# OBC_v4_22.net
KiCad netlist of a schematic drawn in EAGLE
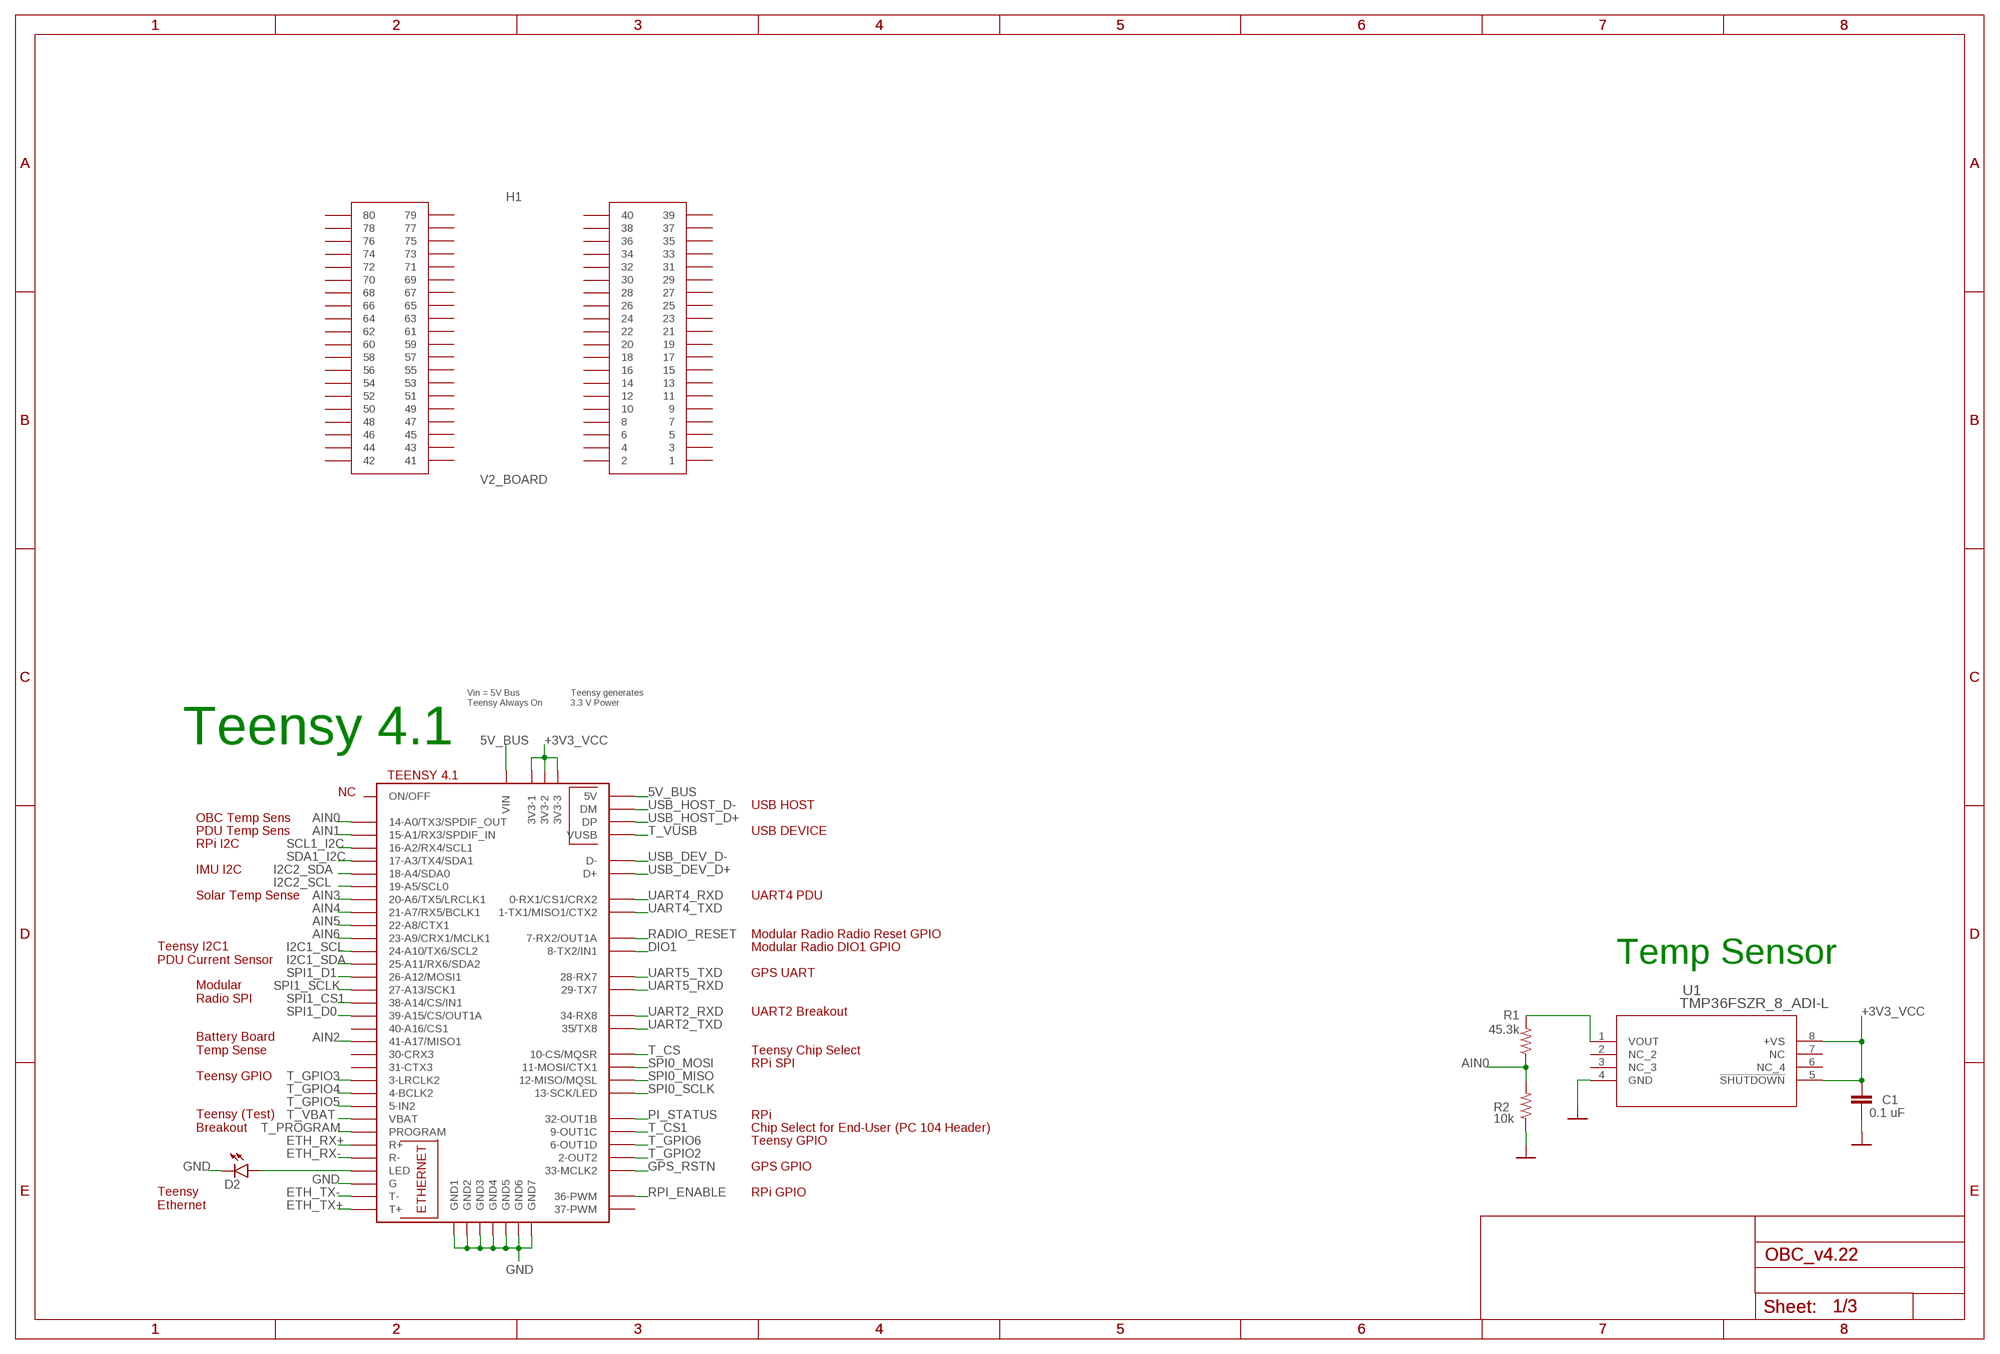
[diagram p0: schematic, sheet 1]
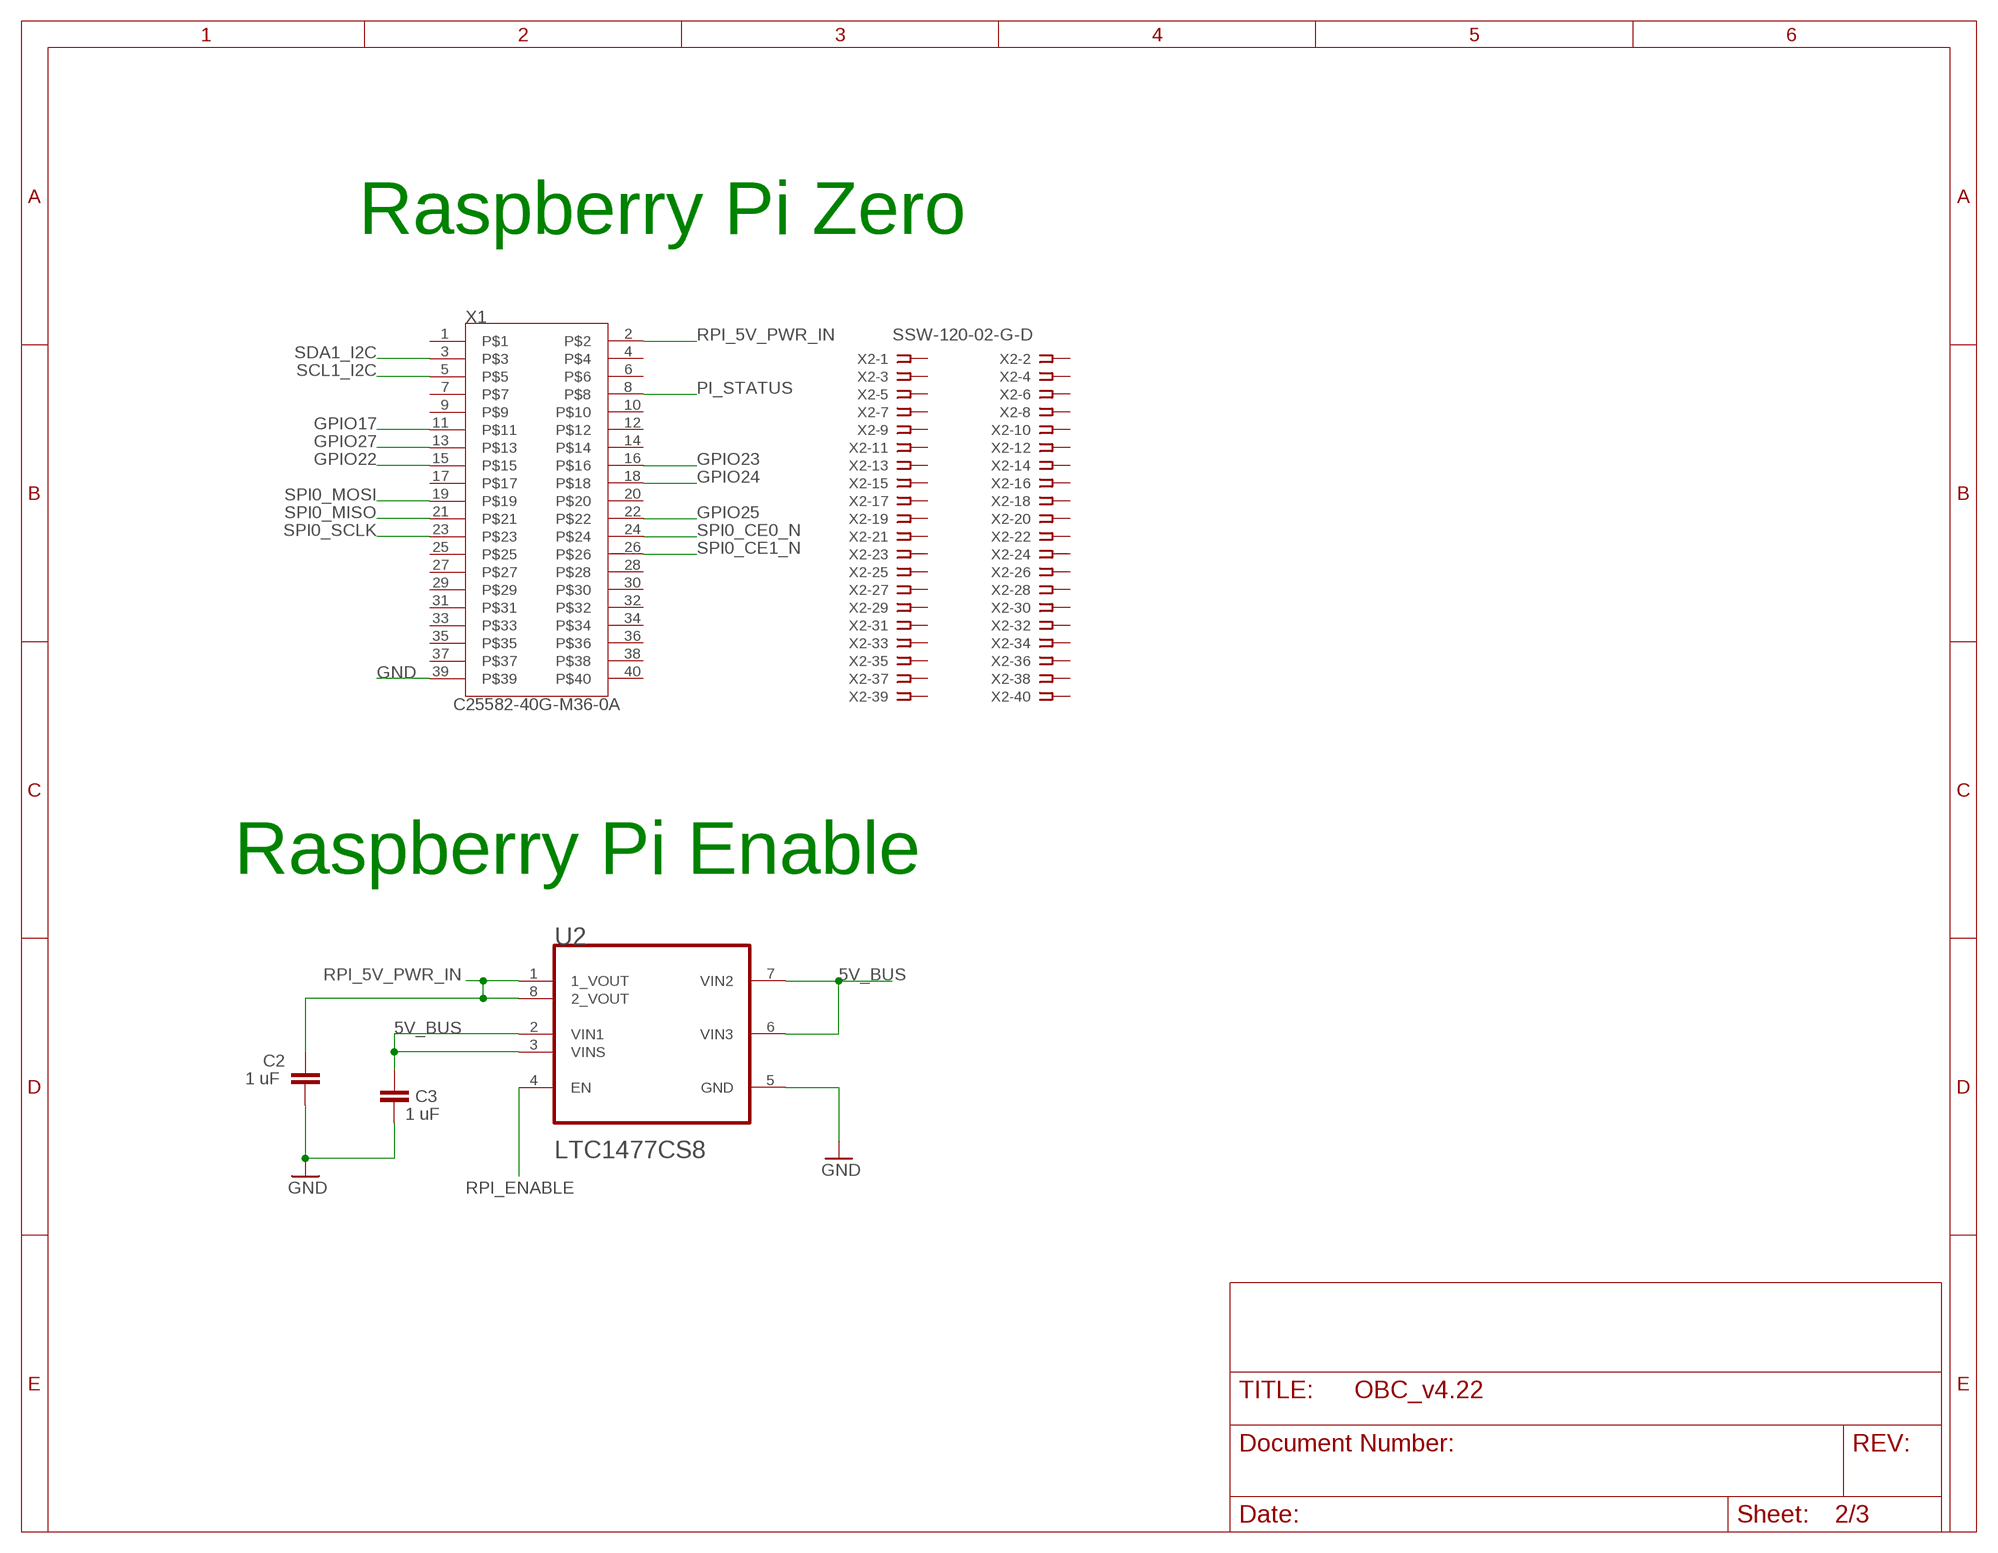
[diagram p1: schematic, sheet 2]
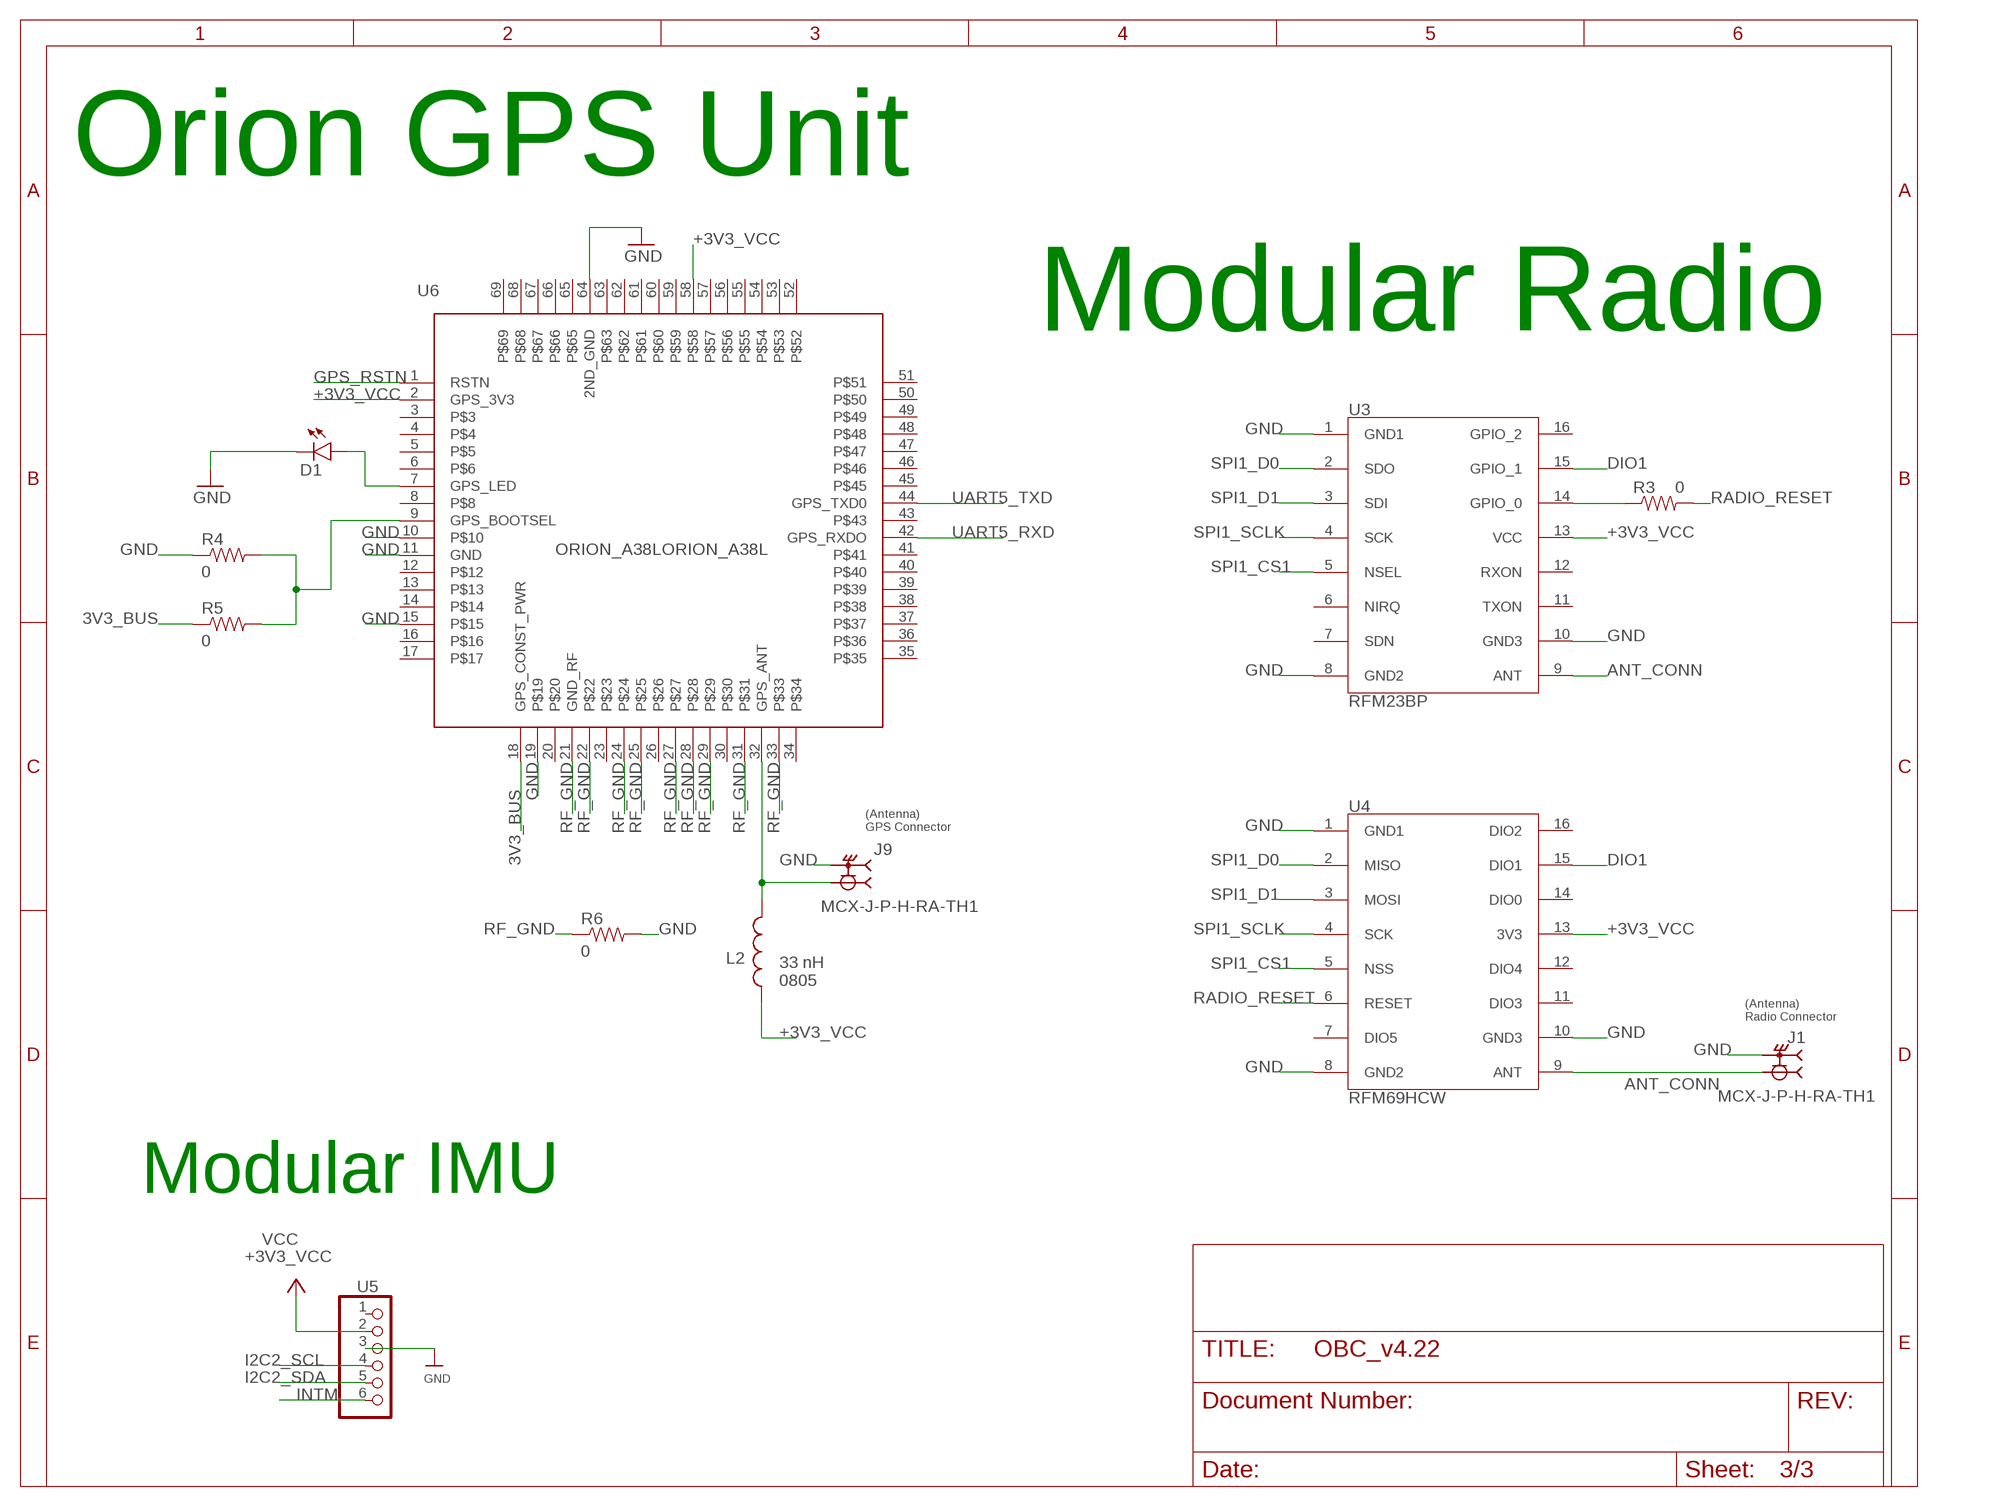
[diagram p2: schematic, sheet 3]

(export (version "E")
  (design (tool "Eeschema 10.0.6"))
  (components
    (comp (ref "C2")
      (value "1 uF")
      (footprint "eagle-import:0805")
      (libsource (lib "eagle-import") (part "CAP0805"))
    )
    (comp (ref "C3")
      (value "1 uF")
      (footprint "eagle-import:0805")
      (libsource (lib "eagle-import") (part "CAP0805"))
    )
    (comp (ref "U2")
      (value "LTC1477CS8LINEAR_TECHNOLOGY_LTC1477CS8_0_2")
      (footprint "eagle-import:LINEAR_TECHNOLOGY_LTC1477CS8_2")
      (fields (field (name "MF") "Linear Technology") (field (name "MPN") "LTC1477CS8"))
      (libsource (lib "eagle-import") (part "LTC1477CS8LINEAR_TECHNOLOGY_LTC1477CS8_0_2"))
    )
    (comp (ref "X1")
      (value "C25582-40G-M36-0A")
      (footprint "eagle-import:ADAFRUIT_C25582-40G-M36-0A_0")
      (libsource (lib "eagle-import") (part "C25582-40G-M36-0A"))
    )
    (comp (ref "X2")
      (value "SSW-120-02-G-D")
      (footprint "eagle-import:SSW-120-02-G-D")
      (fields (field (name "MF") "Samtec Inc."))
      (libsource (lib "eagle-import") (part "SSW-120-02-G-D"))
    )
    (comp (ref "C1")
      (value "0.1 uF")
      (footprint "eagle-import:0805")
      (libsource (lib "eagle-import") (part "CAP0805"))
    )
    (comp (ref "D2")
      (value "LEDCHIP-LED0603")
      (footprint "eagle-import:CHIP-LED0603")
      (libsource (lib "eagle-import") (part "LEDCHIP-LED0603"))
    )
    (comp (ref "H1")
      (value "V2_BOARD")
      (footprint "eagle-import:BOARD_TEMPLATE")
      (libsource (lib "eagle-import") (part "V2_BOARD"))
    )
    (comp (ref "R1")
      (value "45.3k")
      (footprint "eagle-import:0805")
      (libsource (lib "eagle-import") (part "RESISTOR0805-RES"))
    )
    (comp (ref "R2")
      (value "10k")
      (footprint "eagle-import:0805")
      (libsource (lib "eagle-import") (part "RESISTOR0805-RES"))
    )
    (comp (ref "U$1")
      (value "TEENSY41TEENSY")
      (footprint "eagle-import:TEENSY41")
      (libsource (lib "eagle-import") (part "TEENSY41TEENSY"))
    )
    (comp (ref "U1")
      (value "TMP36FSZR_8_ADI-L")
      (footprint "eagle-import:R_8_ADI-L")
      (fields
        (field (name "MANUFACTURER_PART_NUMBER") "TMP36FSZ")
        (field (name "COPYRIGHT") "Copyright (C) 2021 Ultra Librarian. All rights reserved.")
      )
      (libsource (lib "eagle-import") (part "TMP36FSZR_8_ADI-L"))
    )
    (comp (ref "D1")
      (value "LEDCHIP-LED0603")
      (footprint "eagle-import:CHIP-LED0603")
      (libsource (lib "eagle-import") (part "LEDCHIP-LED0603"))
    )
    (comp (ref "J1")
      (value "MCX-J-P-H-RA-TH1")
      (footprint "eagle-import:SAMTEC_MCX-J-P-H-RA-TH1")
      (fields (field (name "DIGI-KEY_PART_NUMBER") "SAM10607-ND") (field (name "MF") "Samtec"))
      (libsource (lib "eagle-import") (part "MCX-J-P-H-RA-TH1"))
    )
    (comp (ref "J9")
      (value "MCX-J-P-H-RA-TH1")
      (footprint "eagle-import:SAMTEC_MCX-J-P-H-RA-TH1")
      (fields (field (name "DIGI-KEY_PART_NUMBER") "SAM10607-ND") (field (name "MF") "Samtec"))
      (libsource (lib "eagle-import") (part "MCX-J-P-H-RA-TH1"))
    )
    (comp (ref "L2")
      (value "AIMC-0805-2N2S-T")
      (footprint "eagle-import:INDC2012X105N")
      (fields (field (name "DIGI-KEY_PART_NUMBER") "535-11562-1-ND") (field (name "MF") "Abracon"))
      (libsource (lib "eagle-import") (part "AIMC-0805-2N2S-T"))
    )
    (comp (ref "R3")
      (value "0")
      (footprint "eagle-import:0805")
      (libsource (lib "eagle-import") (part "RESISTOR0805-RES"))
    )
    (comp (ref "R4")
      (value "0")
      (footprint "eagle-import:0805")
      (libsource (lib "eagle-import") (part "RESISTOR0805-RES"))
    )
    (comp (ref "R5")
      (value "0")
      (footprint "eagle-import:0805")
      (libsource (lib "eagle-import") (part "RESISTOR0805-RES"))
    )
    (comp (ref "R6")
      (value "0")
      (footprint "eagle-import:0805")
      (libsource (lib "eagle-import") (part "RESISTOR0805-RES"))
    )
    (comp (ref "U3")
      (value "RFM23BP")
      (footprint "eagle-import:RFM23BP")
      (libsource (lib "eagle-import") (part "RFM23BP"))
    )
    (comp (ref "U4")
      (value "RFM69HCW")
      (footprint "eagle-import:RFM69HCW")
      (libsource (lib "eagle-import") (part "RFM69HCW"))
    )
    (comp (ref "U5")
      (value "HEADER-1X670MIL")
      (footprint "eagle-import:1X06_ROUND_70")
      (libsource (lib "eagle-import") (part "HEADER-1X670MIL"))
    )
    (comp (ref "U6")
      (value "ORION_A38LORION_A38L")
      (footprint "eagle-import:ORION_A38L")
      (libsource (lib "eagle-import") (part "ORION_A38LORION_A38L"))
    )
  )
  (nets
    (net (code "1") (name "+3V3_VCC") (class "Default")
      (node (ref "C1") (pin "1") (pinfunction "1_1") (pintype "passive"))
      (node (ref "L2") (pin "1") (pinfunction "1_1") (pintype "passive"))
      (node (ref "U$1") (pin "3V3-1") (pinfunction "3V3-1_3V3-1") (pintype "bidirectional"))
      (node (ref "U$1") (pin "3V3-2") (pinfunction "3V3-2_3V3-2") (pintype "bidirectional"))
      (node (ref "U$1") (pin "3V3-3") (pinfunction "3V3-3_3V3-3") (pintype "bidirectional"))
      (node (ref "U1") (pin "5") (pinfunction "~{SHUTDOWN}_5") (pintype "passive"))
      (node (ref "U1") (pin "8") (pinfunction "+VS_8") (pintype "power_in"))
      (node (ref "U3") (pin "13") (pinfunction "VCC_13") (pintype "bidirectional"))
      (node (ref "U4") (pin "13") (pinfunction "3V3_13") (pintype "bidirectional"))
      (node (ref "U5") (pin "2") (pinfunction "2_2") (pintype "passive"))
      (node (ref "U6") (pin "2") (pinfunction "GPS_3V3_2") (pintype "bidirectional"))
      (node (ref "U6") (pin "58") (pinfunction "P$58_58") (pintype "bidirectional"))
    )
    (net (code "2") (name "3V3_BUS") (class "Default")
      (node (ref "R5") (pin "1") (pinfunction "1_1") (pintype "passive"))
      (node (ref "U6") (pin "18") (pinfunction "GPS_CONST_PWR_18") (pintype "bidirectional"))
    )
    (net (code "3") (name "5V_BUS") (class "Default")
      (node (ref "C3") (pin "1") (pinfunction "1_1") (pintype "passive"))
      (node (ref "U$1") (pin "+5V") (pinfunction "5V_+5V") (pintype "bidirectional"))
      (node (ref "U$1") (pin "VIN") (pinfunction "VIN_VIN") (pintype "bidirectional"))
      (node (ref "U2") (pin "2") (pinfunction "VIN1_2") (pintype "power_in"))
      (node (ref "U2") (pin "3") (pinfunction "VINS_3") (pintype "power_in"))
      (node (ref "U2") (pin "6") (pinfunction "VIN3_6") (pintype "power_in"))
      (node (ref "U2") (pin "7") (pinfunction "VIN2_7") (pintype "power_in"))
    )
    (net (code "4") (name "AIN0") (class "Default")
      (node (ref "R1") (pin "1") (pinfunction "1_1") (pintype "passive"))
      (node (ref "R2") (pin "2") (pinfunction "2_2") (pintype "passive"))
      (node (ref "U$1") (pin "14-A0/TX3/SPDIF_OUT") (pinfunction "14-A0/TX3/SPDIF_OUT_14-A0/TX3/SPDIF_OUT") (pintype "bidirectional"))
    )
    (net (code "5") (name "AIN1") (class "Default")
      (node (ref "U$1") (pin "15-A1/RX3/SPDIF_IN") (pinfunction "15-A1/RX3/SPDIF_IN_15-A1/RX3/SPDIF_IN") (pintype "bidirectional"))
    )
    (net (code "6") (name "AIN2") (class "Default")
      (node (ref "U$1") (pin "41-A17/MISO1") (pinfunction "41-A17/MISO1_41-A17/MISO1") (pintype "bidirectional"))
    )
    (net (code "7") (name "AIN3") (class "Default")
      (node (ref "U$1") (pin "20-A6/TX5/LRCLK1") (pinfunction "20-A6/TX5/LRCLK1_20-A6/TX5/LRCLK1") (pintype "bidirectional"))
    )
    (net (code "8") (name "AIN4") (class "Default")
      (node (ref "U$1") (pin "21-A7/RX5/BCLK1") (pinfunction "21-A7/RX5/BCLK1_21-A7/RX5/BCLK1") (pintype "bidirectional"))
    )
    (net (code "9") (name "AIN5") (class "Default")
      (node (ref "U$1") (pin "22-A8/CTX1") (pinfunction "22-A8/CTX1_22-A8/CTX1") (pintype "bidirectional"))
    )
    (net (code "10") (name "AIN6") (class "Default")
      (node (ref "U$1") (pin "23-A9/CRX1/MCLK1") (pinfunction "23-A9/CRX1/MCLK1_23-A9/CRX1/MCLK1") (pintype "bidirectional"))
    )
    (net (code "11") (name "ANT_CONN") (class "Default")
      (node (ref "J1") (pin "1") (pinfunction "1_1") (pintype "passive"))
      (node (ref "U3") (pin "9") (pinfunction "ANT_9") (pintype "bidirectional"))
      (node (ref "U4") (pin "9") (pinfunction "ANT_9") (pintype "bidirectional"))
    )
    (net (code "12") (name "DIO1") (class "Default")
      (node (ref "U$1") (pin "8-TX2/IN1") (pinfunction "8-TX2/IN1_8-TX2/IN1") (pintype "bidirectional"))
      (node (ref "U3") (pin "15") (pinfunction "GPIO_1_15") (pintype "bidirectional"))
      (node (ref "U4") (pin "15") (pinfunction "DIO1_15") (pintype "bidirectional"))
    )
    (net (code "13") (name "ETH_RX+") (class "Default")
      (node (ref "U$1") (pin "R+") (pinfunction "R+_R+") (pintype "bidirectional"))
    )
    (net (code "14") (name "ETH_RX-") (class "Default")
      (node (ref "U$1") (pin "R-") (pinfunction "R-_R-") (pintype "bidirectional"))
    )
    (net (code "15") (name "ETH_TX+") (class "Default")
      (node (ref "U$1") (pin "T+") (pinfunction "T+_T+") (pintype "bidirectional"))
    )
    (net (code "16") (name "ETH_TX-") (class "Default")
      (node (ref "U$1") (pin "T-") (pinfunction "T-_T-") (pintype "bidirectional"))
    )
    (net (code "17") (name "GND") (class "Default")
      (node (ref "C1") (pin "2") (pinfunction "2_2") (pintype "passive"))
      (node (ref "C2") (pin "2") (pinfunction "2_2") (pintype "passive"))
      (node (ref "C3") (pin "2") (pinfunction "2_2") (pintype "passive"))
      (node (ref "D1") (pin "C") (pinfunction "C_C") (pintype "passive"))
      (node (ref "D2") (pin "C") (pinfunction "C_C") (pintype "passive"))
      (node (ref "J1") (pin "S1") (pinfunction "2_S1") (pintype "passive"))
      (node (ref "J1") (pin "S2") (pinfunction "2_S2") (pintype "passive"))
      (node (ref "J1") (pin "S3") (pinfunction "2_S3") (pintype "passive"))
      (node (ref "J1") (pin "S4") (pinfunction "2_S4") (pintype "passive"))
      (node (ref "J9") (pin "S1") (pinfunction "2_S1") (pintype "passive"))
      (node (ref "J9") (pin "S2") (pinfunction "2_S2") (pintype "passive"))
      (node (ref "J9") (pin "S3") (pinfunction "2_S3") (pintype "passive"))
      (node (ref "J9") (pin "S4") (pinfunction "2_S4") (pintype "passive"))
      (node (ref "R2") (pin "1") (pinfunction "1_1") (pintype "passive"))
      (node (ref "R4") (pin "1") (pinfunction "1_1") (pintype "passive"))
      (node (ref "R6") (pin "2") (pinfunction "2_2") (pintype "passive"))
      (node (ref "U$1") (pin "G") (pinfunction "G_G") (pintype "bidirectional"))
      (node (ref "U$1") (pin "GND") (pinfunction "GND7_GND") (pintype "bidirectional"))
      (node (ref "U$1") (pin "GND1") (pinfunction "GND1_GND1") (pintype "bidirectional"))
      (node (ref "U$1") (pin "GND2") (pinfunction "GND2_GND2") (pintype "bidirectional"))
      (node (ref "U$1") (pin "GND3") (pinfunction "GND3_GND3") (pintype "bidirectional"))
      (node (ref "U$1") (pin "GND4") (pinfunction "GND4_GND4") (pintype "bidirectional"))
      (node (ref "U$1") (pin "GND5") (pinfunction "GND5_GND5") (pintype "bidirectional"))
      (node (ref "U$1") (pin "GND6") (pinfunction "GND6_GND6") (pintype "bidirectional"))
      (node (ref "U1") (pin "4") (pinfunction "GND_4") (pintype "passive"))
      (node (ref "U2") (pin "5") (pinfunction "GND_5") (pintype "power_in"))
      (node (ref "U3") (pin "1") (pinfunction "GND1_1") (pintype "bidirectional"))
      (node (ref "U3") (pin "10") (pinfunction "GND3_10") (pintype "bidirectional"))
      (node (ref "U3") (pin "8") (pinfunction "GND2_8") (pintype "bidirectional"))
      (node (ref "U4") (pin "1") (pinfunction "GND1_1") (pintype "bidirectional"))
      (node (ref "U4") (pin "10") (pinfunction "GND3_10") (pintype "bidirectional"))
      (node (ref "U4") (pin "8") (pinfunction "GND2_8") (pintype "bidirectional"))
      (node (ref "U5") (pin "3") (pinfunction "3_3") (pintype "passive"))
      (node (ref "U6") (pin "10") (pinfunction "P$10_10") (pintype "bidirectional"))
      (node (ref "U6") (pin "11") (pinfunction "GND_11") (pintype "bidirectional"))
      (node (ref "U6") (pin "15") (pinfunction "P$15_15") (pintype "bidirectional"))
      (node (ref "U6") (pin "19") (pinfunction "P$19_19") (pintype "bidirectional"))
      (node (ref "U6") (pin "64") (pinfunction "2ND_GND_64") (pintype "bidirectional"))
      (node (ref "X1") (pin "39") (pinfunction "P$39_39") (pintype "bidirectional"))
    )
    (net (code "18") (name "GPIO17") (class "Default")
      (node (ref "X1") (pin "11") (pinfunction "P$11_11") (pintype "bidirectional"))
    )
    (net (code "19") (name "GPIO22") (class "Default")
      (node (ref "X1") (pin "15") (pinfunction "P$15_15") (pintype "bidirectional"))
    )
    (net (code "20") (name "GPIO23") (class "Default")
      (node (ref "X1") (pin "16") (pinfunction "P$16_16") (pintype "bidirectional"))
    )
    (net (code "21") (name "GPIO24") (class "Default")
      (node (ref "X1") (pin "18") (pinfunction "P$18_18") (pintype "bidirectional"))
    )
    (net (code "22") (name "GPIO25") (class "Default")
      (node (ref "X1") (pin "22") (pinfunction "P$22_22") (pintype "bidirectional"))
    )
    (net (code "23") (name "GPIO27") (class "Default")
      (node (ref "X1") (pin "13") (pinfunction "P$13_13") (pintype "bidirectional"))
    )
    (net (code "24") (name "GPS_RSTN") (class "Default")
      (node (ref "U$1") (pin "33-MCLK2") (pinfunction "33-MCLK2_33-MCLK2") (pintype "bidirectional"))
      (node (ref "U6") (pin "1") (pinfunction "RSTN_1") (pintype "bidirectional"))
    )
    (net (code "25") (name "I2C1_SCL") (class "Default")
      (node (ref "U$1") (pin "24-A10/TX6/SCL2") (pinfunction "24-A10/TX6/SCL2_24-A10/TX6/SCL2") (pintype "bidirectional"))
    )
    (net (code "26") (name "I2C1_SDA") (class "Default")
      (node (ref "U$1") (pin "25-A11/RX6/SDA2") (pinfunction "25-A11/RX6/SDA2_25-A11/RX6/SDA2") (pintype "bidirectional"))
    )
    (net (code "27") (name "I2C2_SCL") (class "Default")
      (node (ref "U$1") (pin "19-A5/SCL0") (pinfunction "19-A5/SCL0_19-A5/SCL0") (pintype "bidirectional"))
      (node (ref "U5") (pin "4") (pinfunction "4_4") (pintype "passive"))
    )
    (net (code "28") (name "I2C2_SDA") (class "Default")
      (node (ref "U$1") (pin "18-A4/SDA0") (pinfunction "18-A4/SDA0_18-A4/SDA0") (pintype "bidirectional"))
      (node (ref "U5") (pin "5") (pinfunction "5_5") (pintype "passive"))
    )
    (net (code "29") (name "INTM") (class "Default")
      (node (ref "U5") (pin "6") (pinfunction "6_6") (pintype "passive"))
    )
    (net (code "30") (name "Net-(D2-PadA)") (class "Default")
      (node (ref "D2") (pin "A") (pinfunction "A_A") (pintype "passive"))
      (node (ref "U$1") (pin "LED") (pinfunction "LED_LED") (pintype "bidirectional"))
    )
    (net (code "31") (name "Net-(U1-VOUT)") (class "Default")
      (node (ref "R1") (pin "2") (pinfunction "2_2") (pintype "passive"))
      (node (ref "U1") (pin "1") (pinfunction "VOUT_1") (pintype "output"))
    )
    (net (code "32") (name "Net-(U3-GPIO_0)") (class "Default")
      (node (ref "R3") (pin "1") (pinfunction "1_1") (pintype "passive"))
      (node (ref "U3") (pin "14") (pinfunction "GPIO_0_14") (pintype "bidirectional"))
    )
    (net (code "33") (name "Net-(U6-GPS_ANT)") (class "Default")
      (node (ref "J9") (pin "1") (pinfunction "1_1") (pintype "passive"))
      (node (ref "L2") (pin "2") (pinfunction "2_2") (pintype "passive"))
      (node (ref "U6") (pin "32") (pinfunction "GPS_ANT_32") (pintype "bidirectional"))
    )
    (net (code "34") (name "Net-(U6-GPS_BOOTSEL)") (class "Default")
      (node (ref "R4") (pin "2") (pinfunction "2_2") (pintype "passive"))
      (node (ref "R5") (pin "2") (pinfunction "2_2") (pintype "passive"))
      (node (ref "U6") (pin "9") (pinfunction "GPS_BOOTSEL_9") (pintype "bidirectional"))
    )
    (net (code "35") (name "Net-(U6-GPS_LED)") (class "Default")
      (node (ref "D1") (pin "A") (pinfunction "A_A") (pintype "passive"))
      (node (ref "U6") (pin "7") (pinfunction "GPS_LED_7") (pintype "bidirectional"))
    )
    (net (code "36") (name "PI_STATUS") (class "Default")
      (node (ref "U$1") (pin "32-OUT1B") (pinfunction "32-OUT1B_32-OUT1B") (pintype "bidirectional"))
      (node (ref "X1") (pin "8") (pinfunction "P$8_8") (pintype "bidirectional"))
    )
    (net (code "37") (name "RADIO_RESET") (class "Default")
      (node (ref "R3") (pin "2") (pinfunction "2_2") (pintype "passive"))
      (node (ref "U$1") (pin "7-RX2/OUT1A") (pinfunction "7-RX2/OUT1A_7-RX2/OUT1A") (pintype "bidirectional"))
      (node (ref "U4") (pin "6") (pinfunction "RESET_6") (pintype "bidirectional"))
    )
    (net (code "38") (name "RF_GND") (class "Default")
      (node (ref "R6") (pin "1") (pinfunction "1_1") (pintype "passive"))
      (node (ref "U6") (pin "21") (pinfunction "GND_RF_21") (pintype "bidirectional"))
      (node (ref "U6") (pin "22") (pinfunction "P$22_22") (pintype "bidirectional"))
      (node (ref "U6") (pin "24") (pinfunction "P$24_24") (pintype "bidirectional"))
      (node (ref "U6") (pin "25") (pinfunction "P$25_25") (pintype "bidirectional"))
      (node (ref "U6") (pin "27") (pinfunction "P$27_27") (pintype "bidirectional"))
      (node (ref "U6") (pin "28") (pinfunction "P$28_28") (pintype "bidirectional"))
      (node (ref "U6") (pin "29") (pinfunction "P$29_29") (pintype "bidirectional"))
      (node (ref "U6") (pin "31") (pinfunction "P$31_31") (pintype "bidirectional"))
      (node (ref "U6") (pin "33") (pinfunction "P$33_33") (pintype "bidirectional"))
    )
    (net (code "39") (name "RPI_5V_PWR_IN") (class "Default")
      (node (ref "C2") (pin "1") (pinfunction "1_1") (pintype "passive"))
      (node (ref "U2") (pin "1") (pinfunction "1_VOUT_1") (pintype "power_in"))
      (node (ref "U2") (pin "8") (pinfunction "2_VOUT_8") (pintype "power_in"))
      (node (ref "X1") (pin "2") (pinfunction "P$2_2") (pintype "bidirectional"))
    )
    (net (code "40") (name "RPI_ENABLE") (class "Default")
      (node (ref "U$1") (pin "36-PWM") (pinfunction "36-PWM_36-PWM") (pintype "bidirectional"))
      (node (ref "U2") (pin "4") (pinfunction "EN_4") (pintype "input"))
    )
    (net (code "41") (name "SCL1_I2C") (class "Default")
      (node (ref "U$1") (pin "16-A2/RX4/SCL1") (pinfunction "16-A2/RX4/SCL1_16-A2/RX4/SCL1") (pintype "bidirectional"))
      (node (ref "X1") (pin "5") (pinfunction "P$5_5") (pintype "bidirectional"))
    )
    (net (code "42") (name "SDA1_I2C") (class "Default")
      (node (ref "U$1") (pin "17-A3/TX4/SDA1") (pinfunction "17-A3/TX4/SDA1_17-A3/TX4/SDA1") (pintype "bidirectional"))
      (node (ref "X1") (pin "3") (pinfunction "P$3_3") (pintype "bidirectional"))
    )
    (net (code "43") (name "SPI0_CE0_N") (class "Default")
      (node (ref "X1") (pin "24") (pinfunction "P$24_24") (pintype "bidirectional"))
    )
    (net (code "44") (name "SPI0_CE1_N") (class "Default")
      (node (ref "X1") (pin "26") (pinfunction "P$26_26") (pintype "bidirectional"))
    )
    (net (code "45") (name "SPI0_MISO") (class "Default")
      (node (ref "U$1") (pin "12-MISO/MQSL") (pinfunction "12-MISO/MQSL_12-MISO/MQSL") (pintype "bidirectional"))
      (node (ref "X1") (pin "21") (pinfunction "P$21_21") (pintype "bidirectional"))
    )
    (net (code "46") (name "SPI0_MOSI") (class "Default")
      (node (ref "U$1") (pin "11-MOSI/CTX1") (pinfunction "11-MOSI/CTX1_11-MOSI/CTX1") (pintype "bidirectional"))
      (node (ref "X1") (pin "19") (pinfunction "P$19_19") (pintype "bidirectional"))
    )
    (net (code "47") (name "SPI0_SCLK") (class "Default")
      (node (ref "U$1") (pin "13-SCK/LED") (pinfunction "13-SCK/LED_13-SCK/LED") (pintype "bidirectional"))
      (node (ref "X1") (pin "23") (pinfunction "P$23_23") (pintype "bidirectional"))
    )
    (net (code "48") (name "SPI1_CS1") (class "Default")
      (node (ref "U$1") (pin "38-A14/CS/IN1") (pinfunction "38-A14/CS/IN1_38-A14/CS/IN1") (pintype "bidirectional"))
      (node (ref "U3") (pin "5") (pinfunction "NSEL_5") (pintype "bidirectional"))
      (node (ref "U4") (pin "5") (pinfunction "NSS_5") (pintype "bidirectional"))
    )
    (net (code "49") (name "SPI1_D0") (class "Default")
      (node (ref "U$1") (pin "39-A15/CS/OUT1A") (pinfunction "39-A15/CS/OUT1A_39-A15/CS/OUT1A") (pintype "bidirectional"))
      (node (ref "U3") (pin "2") (pinfunction "SDO_2") (pintype "bidirectional"))
      (node (ref "U4") (pin "2") (pinfunction "MISO_2") (pintype "bidirectional"))
    )
    (net (code "50") (name "SPI1_D1") (class "Default")
      (node (ref "U$1") (pin "26-A12/MOSI1") (pinfunction "26-A12/MOSI1_26-A12/MOSI1") (pintype "bidirectional"))
      (node (ref "U3") (pin "3") (pinfunction "SDI_3") (pintype "bidirectional"))
      (node (ref "U4") (pin "3") (pinfunction "MOSI_3") (pintype "bidirectional"))
    )
    (net (code "51") (name "SPI1_SCLK") (class "Default")
      (node (ref "U$1") (pin "27-A13/SCK1") (pinfunction "27-A13/SCK1_27-A13/SCK1") (pintype "bidirectional"))
      (node (ref "U3") (pin "4") (pinfunction "SCK_4") (pintype "bidirectional"))
      (node (ref "U4") (pin "4") (pinfunction "SCK_4") (pintype "bidirectional"))
    )
    (net (code "52") (name "T_CS") (class "Default")
      (node (ref "U$1") (pin "10-CS\\MQSR") (pinfunction "10-CS/MQSR_10-CS\\MQSR") (pintype "bidirectional"))
    )
    (net (code "53") (name "T_CS1") (class "Default")
      (node (ref "U$1") (pin "9-OUT1C") (pinfunction "9-OUT1C_9-OUT1C") (pintype "bidirectional"))
    )
    (net (code "54") (name "T_GPIO2") (class "Default")
      (node (ref "U$1") (pin "2-OUT2") (pinfunction "2-OUT2_2-OUT2") (pintype "bidirectional"))
    )
    (net (code "55") (name "T_GPIO3") (class "Default")
      (node (ref "U$1") (pin "3-LRCLK2") (pinfunction "3-LRCLK2_3-LRCLK2") (pintype "bidirectional"))
    )
    (net (code "56") (name "T_GPIO4") (class "Default")
      (node (ref "U$1") (pin "4-BCLK2") (pinfunction "4-BCLK2_4-BCLK2") (pintype "bidirectional"))
    )
    (net (code "57") (name "T_GPIO5") (class "Default")
      (node (ref "U$1") (pin "5-IN2") (pinfunction "5-IN2_5-IN2") (pintype "bidirectional"))
    )
    (net (code "58") (name "T_GPIO6") (class "Default")
      (node (ref "U$1") (pin "6-OUT1D") (pinfunction "6-OUT1D_6-OUT1D") (pintype "bidirectional"))
    )
    (net (code "59") (name "T_PROGRAM") (class "Default")
      (node (ref "U$1") (pin "PROGRAM") (pinfunction "PROGRAM_PROGRAM") (pintype "bidirectional"))
    )
    (net (code "60") (name "T_VBAT") (class "Default")
      (node (ref "U$1") (pin "VBAT") (pinfunction "VBAT_VBAT") (pintype "bidirectional"))
    )
    (net (code "61") (name "T_VUSB") (class "Default")
      (node (ref "U$1") (pin "VUSB") (pinfunction "VUSB_VUSB") (pintype "bidirectional"))
    )
    (net (code "62") (name "UART2_RXD") (class "Default")
      (node (ref "U$1") (pin "34-RX8") (pinfunction "34-RX8_34-RX8") (pintype "bidirectional"))
    )
    (net (code "63") (name "UART2_TXD") (class "Default")
      (node (ref "U$1") (pin "35-TX8") (pinfunction "35/TX8_35-TX8") (pintype "bidirectional"))
    )
    (net (code "64") (name "UART4_RXD") (class "Default")
      (node (ref "U$1") (pin "0-RX1/CS1/CRX2") (pinfunction "0-RX1/CS1/CRX2_0-RX1/CS1/CRX2") (pintype "bidirectional"))
    )
    (net (code "65") (name "UART4_TXD") (class "Default")
      (node (ref "U$1") (pin "1-TX1/MISO1/CTX2") (pinfunction "1-TX1/MISO1/CTX2_1-TX1/MISO1/CTX2") (pintype "bidirectional"))
    )
    (net (code "66") (name "UART5_RXD") (class "Default")
      (node (ref "U$1") (pin "29-TX7") (pinfunction "29-TX7_29-TX7") (pintype "bidirectional"))
      (node (ref "U6") (pin "42") (pinfunction "GPS_RXDO_42") (pintype "input"))
    )
    (net (code "67") (name "UART5_TXD") (class "Default")
      (node (ref "U$1") (pin "28-RX7") (pinfunction "28-RX7_28-RX7") (pintype "bidirectional"))
      (node (ref "U6") (pin "44") (pinfunction "GPS_TXD0_44") (pintype "output"))
    )
    (net (code "68") (name "USB_DEV_D+") (class "Default")
      (node (ref "U$1") (pin "D+") (pinfunction "D+_D+") (pintype "bidirectional"))
    )
    (net (code "69") (name "USB_DEV_D-") (class "Default")
      (node (ref "U$1") (pin "D-") (pinfunction "D-_D-") (pintype "bidirectional"))
    )
    (net (code "70") (name "USB_HOST_D+") (class "Default")
      (node (ref "U$1") (pin "DP") (pinfunction "DP_DP") (pintype "bidirectional"))
    )
    (net (code "71") (name "USB_HOST_D-") (class "Default")
      (node (ref "U$1") (pin "DM") (pinfunction "DM_DM") (pintype "bidirectional"))
    )
    (net (code "72") (name "unconnected-(H1-Pad1)") (class "Default")
      (node (ref "H1") (pin "1") (pinfunction "1_1") (pintype "bidirectional"))
    )
    (net (code "73") (name "unconnected-(H1-Pad2)") (class "Default")
      (node (ref "H1") (pin "2") (pinfunction "2_2") (pintype "bidirectional"))
    )
    (net (code "74") (name "unconnected-(H1-Pad3)") (class "Default")
      (node (ref "H1") (pin "3") (pinfunction "3_3") (pintype "bidirectional"))
    )
    (net (code "75") (name "unconnected-(H1-Pad4)") (class "Default")
      (node (ref "H1") (pin "4") (pinfunction "4_4") (pintype "bidirectional"))
    )
    (net (code "76") (name "unconnected-(H1-Pad5)") (class "Default")
      (node (ref "H1") (pin "5") (pinfunction "5_5") (pintype "bidirectional"))
    )
    (net (code "77") (name "unconnected-(H1-Pad6)") (class "Default")
      (node (ref "H1") (pin "6") (pinfunction "6_6") (pintype "bidirectional"))
    )
    (net (code "78") (name "unconnected-(H1-Pad7)") (class "Default")
      (node (ref "H1") (pin "7") (pinfunction "7_7") (pintype "bidirectional"))
    )
    (net (code "79") (name "unconnected-(H1-Pad8)") (class "Default")
      (node (ref "H1") (pin "8") (pinfunction "8_8") (pintype "bidirectional"))
    )
    (net (code "80") (name "unconnected-(H1-Pad9)") (class "Default")
      (node (ref "H1") (pin "9") (pinfunction "9_9") (pintype "bidirectional"))
    )
    (net (code "81") (name "unconnected-(H1-Pad10)") (class "Default")
      (node (ref "H1") (pin "10") (pinfunction "10_10") (pintype "bidirectional"))
    )
    (net (code "82") (name "unconnected-(H1-Pad11)") (class "Default")
      (node (ref "H1") (pin "11") (pinfunction "11_11") (pintype "bidirectional"))
    )
    (net (code "83") (name "unconnected-(H1-Pad12)") (class "Default")
      (node (ref "H1") (pin "12") (pinfunction "12_12") (pintype "bidirectional"))
    )
    (net (code "84") (name "unconnected-(H1-Pad13)") (class "Default")
      (node (ref "H1") (pin "13") (pinfunction "13_13") (pintype "bidirectional"))
    )
    (net (code "85") (name "unconnected-(H1-Pad14)") (class "Default")
      (node (ref "H1") (pin "14") (pinfunction "14_14") (pintype "bidirectional"))
    )
    (net (code "86") (name "unconnected-(H1-Pad15)") (class "Default")
      (node (ref "H1") (pin "15") (pinfunction "15_15") (pintype "bidirectional"))
    )
    (net (code "87") (name "unconnected-(H1-Pad16)") (class "Default")
      (node (ref "H1") (pin "16") (pinfunction "16_16") (pintype "bidirectional"))
    )
    (net (code "88") (name "unconnected-(H1-Pad17)") (class "Default")
      (node (ref "H1") (pin "17") (pinfunction "17_17") (pintype "bidirectional"))
    )
    (net (code "89") (name "unconnected-(H1-Pad18)") (class "Default")
      (node (ref "H1") (pin "18") (pinfunction "18_18") (pintype "bidirectional"))
    )
    (net (code "90") (name "unconnected-(H1-Pad19)") (class "Default")
      (node (ref "H1") (pin "19") (pinfunction "19_19") (pintype "bidirectional"))
    )
    (net (code "91") (name "unconnected-(H1-Pad20)") (class "Default")
      (node (ref "H1") (pin "20") (pinfunction "20_20") (pintype "bidirectional"))
    )
    (net (code "92") (name "unconnected-(H1-Pad21)") (class "Default")
      (node (ref "H1") (pin "21") (pinfunction "21_21") (pintype "bidirectional"))
    )
    (net (code "93") (name "unconnected-(H1-Pad22)") (class "Default")
      (node (ref "H1") (pin "22") (pinfunction "22_22") (pintype "bidirectional"))
    )
    (net (code "94") (name "unconnected-(H1-Pad23)") (class "Default")
      (node (ref "H1") (pin "23") (pinfunction "23_23") (pintype "bidirectional"))
    )
    (net (code "95") (name "unconnected-(H1-Pad24)") (class "Default")
      (node (ref "H1") (pin "24") (pinfunction "24_24") (pintype "bidirectional"))
    )
    (net (code "96") (name "unconnected-(H1-Pad25)") (class "Default")
      (node (ref "H1") (pin "25") (pinfunction "25_25") (pintype "bidirectional"))
    )
    (net (code "97") (name "unconnected-(H1-Pad26)") (class "Default")
      (node (ref "H1") (pin "26") (pinfunction "26_26") (pintype "bidirectional"))
    )
    (net (code "98") (name "unconnected-(H1-Pad27)") (class "Default")
      (node (ref "H1") (pin "27") (pinfunction "27_27") (pintype "bidirectional"))
    )
    (net (code "99") (name "unconnected-(H1-Pad28)") (class "Default")
      (node (ref "H1") (pin "28") (pinfunction "28_28") (pintype "bidirectional"))
    )
    (net (code "100") (name "unconnected-(H1-Pad29)") (class "Default")
      (node (ref "H1") (pin "29") (pinfunction "29_29") (pintype "bidirectional"))
    )
    (net (code "101") (name "unconnected-(H1-Pad30)") (class "Default")
      (node (ref "H1") (pin "30") (pinfunction "30_30") (pintype "bidirectional"))
    )
    (net (code "102") (name "unconnected-(H1-Pad31)") (class "Default")
      (node (ref "H1") (pin "31") (pinfunction "31_31") (pintype "bidirectional"))
    )
    (net (code "103") (name "unconnected-(H1-Pad32)") (class "Default")
      (node (ref "H1") (pin "32") (pinfunction "32_32") (pintype "bidirectional"))
    )
    (net (code "104") (name "unconnected-(H1-Pad33)") (class "Default")
      (node (ref "H1") (pin "33") (pinfunction "33_33") (pintype "bidirectional"))
    )
    (net (code "105") (name "unconnected-(H1-Pad34)") (class "Default")
      (node (ref "H1") (pin "34") (pinfunction "34_34") (pintype "bidirectional"))
    )
    (net (code "106") (name "unconnected-(H1-Pad35)") (class "Default")
      (node (ref "H1") (pin "35") (pinfunction "35_35") (pintype "bidirectional"))
    )
    (net (code "107") (name "unconnected-(H1-Pad36)") (class "Default")
      (node (ref "H1") (pin "36") (pinfunction "36_36") (pintype "bidirectional"))
    )
    (net (code "108") (name "unconnected-(H1-Pad37)") (class "Default")
      (node (ref "H1") (pin "37") (pinfunction "37_37") (pintype "bidirectional"))
    )
    (net (code "109") (name "unconnected-(H1-Pad38)") (class "Default")
      (node (ref "H1") (pin "38") (pinfunction "38_38") (pintype "bidirectional"))
    )
    (net (code "110") (name "unconnected-(H1-Pad39)") (class "Default")
      (node (ref "H1") (pin "39") (pinfunction "39_39") (pintype "bidirectional"))
    )
    (net (code "111") (name "unconnected-(H1-Pad40)") (class "Default")
      (node (ref "H1") (pin "40") (pinfunction "40_40") (pintype "bidirectional"))
    )
    (net (code "112") (name "unconnected-(H1-Pad41)") (class "Default")
      (node (ref "H1") (pin "41") (pinfunction "41_41") (pintype "bidirectional"))
    )
    (net (code "113") (name "unconnected-(H1-Pad42)") (class "Default")
      (node (ref "H1") (pin "42") (pinfunction "42_42") (pintype "bidirectional"))
    )
    (net (code "114") (name "unconnected-(H1-Pad43)") (class "Default")
      (node (ref "H1") (pin "43") (pinfunction "43_43") (pintype "bidirectional"))
    )
    (net (code "115") (name "unconnected-(H1-Pad44)") (class "Default")
      (node (ref "H1") (pin "44") (pinfunction "44_44") (pintype "bidirectional"))
    )
    (net (code "116") (name "unconnected-(H1-Pad45)") (class "Default")
      (node (ref "H1") (pin "45") (pinfunction "45_45") (pintype "bidirectional"))
    )
    (net (code "117") (name "unconnected-(H1-Pad46)") (class "Default")
      (node (ref "H1") (pin "46") (pinfunction "46_46") (pintype "bidirectional"))
    )
    (net (code "118") (name "unconnected-(H1-Pad47)") (class "Default")
      (node (ref "H1") (pin "47") (pinfunction "47_47") (pintype "bidirectional"))
    )
    (net (code "119") (name "unconnected-(H1-Pad48)") (class "Default")
      (node (ref "H1") (pin "48") (pinfunction "48_48") (pintype "bidirectional"))
    )
    (net (code "120") (name "unconnected-(H1-Pad49)") (class "Default")
      (node (ref "H1") (pin "49") (pinfunction "49_49") (pintype "bidirectional"))
    )
    (net (code "121") (name "unconnected-(H1-Pad50)") (class "Default")
      (node (ref "H1") (pin "50") (pinfunction "50_50") (pintype "bidirectional"))
    )
    (net (code "122") (name "unconnected-(H1-Pad51)") (class "Default")
      (node (ref "H1") (pin "51") (pinfunction "51_51") (pintype "bidirectional"))
    )
    (net (code "123") (name "unconnected-(H1-Pad52)") (class "Default")
      (node (ref "H1") (pin "52") (pinfunction "52_52") (pintype "bidirectional"))
    )
    (net (code "124") (name "unconnected-(H1-Pad53)") (class "Default")
      (node (ref "H1") (pin "53") (pinfunction "53_53") (pintype "bidirectional"))
    )
    (net (code "125") (name "unconnected-(H1-Pad54)") (class "Default")
      (node (ref "H1") (pin "54") (pinfunction "54_54") (pintype "bidirectional"))
    )
    (net (code "126") (name "unconnected-(H1-Pad55)") (class "Default")
      (node (ref "H1") (pin "55") (pinfunction "55_55") (pintype "bidirectional"))
    )
    (net (code "127") (name "unconnected-(H1-Pad56)") (class "Default")
      (node (ref "H1") (pin "56") (pinfunction "56_56") (pintype "bidirectional"))
    )
    (net (code "128") (name "unconnected-(H1-Pad57)") (class "Default")
      (node (ref "H1") (pin "57") (pinfunction "57_57") (pintype "bidirectional"))
    )
    (net (code "129") (name "unconnected-(H1-Pad58)") (class "Default")
      (node (ref "H1") (pin "58") (pinfunction "58_58") (pintype "bidirectional"))
    )
    (net (code "130") (name "unconnected-(H1-Pad59)") (class "Default")
      (node (ref "H1") (pin "59") (pinfunction "59_59") (pintype "bidirectional"))
    )
    (net (code "131") (name "unconnected-(H1-Pad60)") (class "Default")
      (node (ref "H1") (pin "60") (pinfunction "60_60") (pintype "bidirectional"))
    )
    (net (code "132") (name "unconnected-(H1-Pad61)") (class "Default")
      (node (ref "H1") (pin "61") (pinfunction "61_61") (pintype "bidirectional"))
    )
    (net (code "133") (name "unconnected-(H1-Pad62)") (class "Default")
      (node (ref "H1") (pin "62") (pinfunction "62_62") (pintype "bidirectional"))
    )
    (net (code "134") (name "unconnected-(H1-Pad63)") (class "Default")
      (node (ref "H1") (pin "63") (pinfunction "63_63") (pintype "bidirectional"))
    )
    (net (code "135") (name "unconnected-(H1-Pad64)") (class "Default")
      (node (ref "H1") (pin "64") (pinfunction "64_64") (pintype "bidirectional"))
    )
    (net (code "136") (name "unconnected-(H1-Pad65)") (class "Default")
      (node (ref "H1") (pin "65") (pinfunction "65_65") (pintype "bidirectional"))
    )
    (net (code "137") (name "unconnected-(H1-Pad66)") (class "Default")
      (node (ref "H1") (pin "66") (pinfunction "66_66") (pintype "bidirectional"))
    )
    (net (code "138") (name "unconnected-(H1-Pad67)") (class "Default")
      (node (ref "H1") (pin "67") (pinfunction "67_67") (pintype "bidirectional"))
    )
    (net (code "139") (name "unconnected-(H1-Pad68)") (class "Default")
      (node (ref "H1") (pin "68") (pinfunction "68_68") (pintype "bidirectional"))
    )
    (net (code "140") (name "unconnected-(H1-Pad69)") (class "Default")
      (node (ref "H1") (pin "69") (pinfunction "69_69") (pintype "bidirectional"))
    )
    (net (code "141") (name "unconnected-(H1-Pad70)") (class "Default")
      (node (ref "H1") (pin "70") (pinfunction "70_70") (pintype "bidirectional"))
    )
    (net (code "142") (name "unconnected-(H1-Pad71)") (class "Default")
      (node (ref "H1") (pin "71") (pinfunction "71_71") (pintype "bidirectional"))
    )
    (net (code "143") (name "unconnected-(H1-Pad72)") (class "Default")
      (node (ref "H1") (pin "72") (pinfunction "72_72") (pintype "bidirectional"))
    )
    (net (code "144") (name "unconnected-(H1-Pad73)") (class "Default")
      (node (ref "H1") (pin "73") (pinfunction "73_73") (pintype "bidirectional"))
    )
    (net (code "145") (name "unconnected-(H1-Pad74)") (class "Default")
      (node (ref "H1") (pin "74") (pinfunction "74_74") (pintype "bidirectional"))
    )
    (net (code "146") (name "unconnected-(H1-Pad75)") (class "Default")
      (node (ref "H1") (pin "75") (pinfunction "75_75") (pintype "bidirectional"))
    )
    (net (code "147") (name "unconnected-(H1-Pad76)") (class "Default")
      (node (ref "H1") (pin "76") (pinfunction "76_76") (pintype "bidirectional"))
    )
    (net (code "148") (name "unconnected-(H1-Pad77)") (class "Default")
      (node (ref "H1") (pin "77") (pinfunction "77_77") (pintype "bidirectional"))
    )
    (net (code "149") (name "unconnected-(H1-Pad78)") (class "Default")
      (node (ref "H1") (pin "78") (pinfunction "78_78") (pintype "bidirectional"))
    )
    (net (code "150") (name "unconnected-(H1-Pad79)") (class "Default")
      (node (ref "H1") (pin "79") (pinfunction "79_79") (pintype "bidirectional"))
    )
    (net (code "151") (name "unconnected-(H1-Pad80)") (class "Default")
      (node (ref "H1") (pin "80") (pinfunction "80_80") (pintype "bidirectional"))
    )
    (net (code "152") (name "unconnected-(U$1-Pad30-CRX3)") (class "Default")
      (node (ref "U$1") (pin "30-CRX3") (pinfunction "30-CRX3_30-CRX3") (pintype "bidirectional"))
    )
    (net (code "153") (name "unconnected-(U$1-Pad31-CTX3)") (class "Default")
      (node (ref "U$1") (pin "31-CTX3") (pinfunction "31-CTX3_31-CTX3") (pintype "bidirectional"))
    )
    (net (code "154") (name "unconnected-(U$1-Pad37-PWM)") (class "Default")
      (node (ref "U$1") (pin "37-PWM") (pinfunction "37-PWM_37-PWM") (pintype "bidirectional"))
    )
    (net (code "155") (name "unconnected-(U$1-Pad40-A16{slash}CS1)") (class "Default")
      (node (ref "U$1") (pin "40-A16/CS1") (pinfunction "40-A16/CS1_40-A16/CS1") (pintype "bidirectional"))
    )
    (net (code "156") (name "unconnected-(U$1-PadON{slash}OFF)") (class "Default")
      (node (ref "U$1") (pin "ON/OFF") (pinfunction "ON/OFF_ON/OFF") (pintype "bidirectional"))
    )
    (net (code "157") (name "unconnected-(U1-NC-Pad7)") (class "Default")
      (node (ref "U1") (pin "7") (pinfunction "NC_7") (pintype "no_connect"))
    )
    (net (code "158") (name "unconnected-(U1-NC_2-Pad2)") (class "Default")
      (node (ref "U1") (pin "2") (pinfunction "NC_2_2") (pintype "no_connect"))
    )
    (net (code "159") (name "unconnected-(U1-NC_3-Pad3)") (class "Default")
      (node (ref "U1") (pin "3") (pinfunction "NC_3_3") (pintype "no_connect"))
    )
    (net (code "160") (name "unconnected-(U1-NC_4-Pad6)") (class "Default")
      (node (ref "U1") (pin "6") (pinfunction "NC_4_6") (pintype "no_connect"))
    )
    (net (code "161") (name "unconnected-(U3-GPIO_2-Pad16)") (class "Default")
      (node (ref "U3") (pin "16") (pinfunction "GPIO_2_16") (pintype "bidirectional"))
    )
    (net (code "162") (name "unconnected-(U3-NIRQ-Pad6)") (class "Default")
      (node (ref "U3") (pin "6") (pinfunction "NIRQ_6") (pintype "bidirectional"))
    )
    (net (code "163") (name "unconnected-(U3-RXON-Pad12)") (class "Default")
      (node (ref "U3") (pin "12") (pinfunction "RXON_12") (pintype "bidirectional"))
    )
    (net (code "164") (name "unconnected-(U3-SDN-Pad7)") (class "Default")
      (node (ref "U3") (pin "7") (pinfunction "SDN_7") (pintype "bidirectional"))
    )
    (net (code "165") (name "unconnected-(U3-TXON-Pad11)") (class "Default")
      (node (ref "U3") (pin "11") (pinfunction "TXON_11") (pintype "bidirectional"))
    )
    (net (code "166") (name "unconnected-(U4-DIO0-Pad14)") (class "Default")
      (node (ref "U4") (pin "14") (pinfunction "DIO0_14") (pintype "bidirectional"))
    )
    (net (code "167") (name "unconnected-(U4-DIO2-Pad16)") (class "Default")
      (node (ref "U4") (pin "16") (pinfunction "DIO2_16") (pintype "bidirectional"))
    )
    (net (code "168") (name "unconnected-(U4-DIO3-Pad11)") (class "Default")
      (node (ref "U4") (pin "11") (pinfunction "DIO3_11") (pintype "bidirectional"))
    )
    (net (code "169") (name "unconnected-(U4-DIO4-Pad12)") (class "Default")
      (node (ref "U4") (pin "12") (pinfunction "DIO4_12") (pintype "bidirectional"))
    )
    (net (code "170") (name "unconnected-(U4-DIO5-Pad7)") (class "Default")
      (node (ref "U4") (pin "7") (pinfunction "DIO5_7") (pintype "bidirectional"))
    )
    (net (code "171") (name "unconnected-(U5-Pad1)") (class "Default")
      (node (ref "U5") (pin "1") (pinfunction "1_1") (pintype "passive"))
    )
    (net (code "172") (name "unconnected-(U6-P$3-Pad3)") (class "Default")
      (node (ref "U6") (pin "3") (pinfunction "P$3_3") (pintype "bidirectional"))
    )
    (net (code "173") (name "unconnected-(U6-P$4-Pad4)") (class "Default")
      (node (ref "U6") (pin "4") (pinfunction "P$4_4") (pintype "bidirectional"))
    )
    (net (code "174") (name "unconnected-(U6-P$5-Pad5)") (class "Default")
      (node (ref "U6") (pin "5") (pinfunction "P$5_5") (pintype "bidirectional"))
    )
    (net (code "175") (name "unconnected-(U6-P$6-Pad6)") (class "Default")
      (node (ref "U6") (pin "6") (pinfunction "P$6_6") (pintype "bidirectional"))
    )
    (net (code "176") (name "unconnected-(U6-P$8-Pad8)") (class "Default")
      (node (ref "U6") (pin "8") (pinfunction "P$8_8") (pintype "bidirectional"))
    )
    (net (code "177") (name "unconnected-(U6-P$12-Pad12)") (class "Default")
      (node (ref "U6") (pin "12") (pinfunction "P$12_12") (pintype "bidirectional"))
    )
    (net (code "178") (name "unconnected-(U6-P$13-Pad13)") (class "Default")
      (node (ref "U6") (pin "13") (pinfunction "P$13_13") (pintype "bidirectional"))
    )
    (net (code "179") (name "unconnected-(U6-P$14-Pad14)") (class "Default")
      (node (ref "U6") (pin "14") (pinfunction "P$14_14") (pintype "bidirectional"))
    )
    (net (code "180") (name "unconnected-(U6-P$16-Pad16)") (class "Default")
      (node (ref "U6") (pin "16") (pinfunction "P$16_16") (pintype "bidirectional"))
    )
    (net (code "181") (name "unconnected-(U6-P$17-Pad17)") (class "Default")
      (node (ref "U6") (pin "17") (pinfunction "P$17_17") (pintype "bidirectional"))
    )
    (net (code "182") (name "unconnected-(U6-P$20-Pad20)") (class "Default")
      (node (ref "U6") (pin "20") (pinfunction "P$20_20") (pintype "bidirectional"))
    )
    (net (code "183") (name "unconnected-(U6-P$23-Pad23)") (class "Default")
      (node (ref "U6") (pin "23") (pinfunction "P$23_23") (pintype "bidirectional"))
    )
    (net (code "184") (name "unconnected-(U6-P$26-Pad26)") (class "Default")
      (node (ref "U6") (pin "26") (pinfunction "P$26_26") (pintype "bidirectional"))
    )
    (net (code "185") (name "unconnected-(U6-P$30-Pad30)") (class "Default")
      (node (ref "U6") (pin "30") (pinfunction "P$30_30") (pintype "bidirectional"))
    )
    (net (code "186") (name "unconnected-(U6-P$34-Pad34)") (class "Default")
      (node (ref "U6") (pin "34") (pinfunction "P$34_34") (pintype "bidirectional"))
    )
    (net (code "187") (name "unconnected-(U6-P$35-Pad35)") (class "Default")
      (node (ref "U6") (pin "35") (pinfunction "P$35_35") (pintype "bidirectional"))
    )
    (net (code "188") (name "unconnected-(U6-P$36-Pad36)") (class "Default")
      (node (ref "U6") (pin "36") (pinfunction "P$36_36") (pintype "bidirectional"))
    )
    (net (code "189") (name "unconnected-(U6-P$37-Pad37)") (class "Default")
      (node (ref "U6") (pin "37") (pinfunction "P$37_37") (pintype "bidirectional"))
    )
    (net (code "190") (name "unconnected-(U6-P$38-Pad38)") (class "Default")
      (node (ref "U6") (pin "38") (pinfunction "P$38_38") (pintype "bidirectional"))
    )
    (net (code "191") (name "unconnected-(U6-P$39-Pad39)") (class "Default")
      (node (ref "U6") (pin "39") (pinfunction "P$39_39") (pintype "bidirectional"))
    )
    (net (code "192") (name "unconnected-(U6-P$40-Pad40)") (class "Default")
      (node (ref "U6") (pin "40") (pinfunction "P$40_40") (pintype "bidirectional"))
    )
    (net (code "193") (name "unconnected-(U6-P$41-Pad41)") (class "Default")
      (node (ref "U6") (pin "41") (pinfunction "P$41_41") (pintype "bidirectional"))
    )
    (net (code "194") (name "unconnected-(U6-P$43-Pad43)") (class "Default")
      (node (ref "U6") (pin "43") (pinfunction "P$43_43") (pintype "bidirectional"))
    )
    (net (code "195") (name "unconnected-(U6-P$45-Pad45)") (class "Default")
      (node (ref "U6") (pin "45") (pinfunction "P$45_45") (pintype "bidirectional"))
    )
    (net (code "196") (name "unconnected-(U6-P$46-Pad46)") (class "Default")
      (node (ref "U6") (pin "46") (pinfunction "P$46_46") (pintype "bidirectional"))
    )
    (net (code "197") (name "unconnected-(U6-P$47-Pad47)") (class "Default")
      (node (ref "U6") (pin "47") (pinfunction "P$47_47") (pintype "bidirectional"))
    )
    (net (code "198") (name "unconnected-(U6-P$48-Pad48)") (class "Default")
      (node (ref "U6") (pin "48") (pinfunction "P$48_48") (pintype "bidirectional"))
    )
    (net (code "199") (name "unconnected-(U6-P$49-Pad49)") (class "Default")
      (node (ref "U6") (pin "49") (pinfunction "P$49_49") (pintype "bidirectional"))
    )
    (net (code "200") (name "unconnected-(U6-P$50-Pad50)") (class "Default")
      (node (ref "U6") (pin "50") (pinfunction "P$50_50") (pintype "bidirectional"))
    )
    (net (code "201") (name "unconnected-(U6-P$51-Pad51)") (class "Default")
      (node (ref "U6") (pin "51") (pinfunction "P$51_51") (pintype "bidirectional"))
    )
    (net (code "202") (name "unconnected-(U6-P$52-Pad52)") (class "Default")
      (node (ref "U6") (pin "52") (pinfunction "P$52_52") (pintype "bidirectional"))
    )
    (net (code "203") (name "unconnected-(U6-P$53-Pad53)") (class "Default")
      (node (ref "U6") (pin "53") (pinfunction "P$53_53") (pintype "bidirectional"))
    )
    (net (code "204") (name "unconnected-(U6-P$54-Pad54)") (class "Default")
      (node (ref "U6") (pin "54") (pinfunction "P$54_54") (pintype "bidirectional"))
    )
    (net (code "205") (name "unconnected-(U6-P$55-Pad55)") (class "Default")
      (node (ref "U6") (pin "55") (pinfunction "P$55_55") (pintype "bidirectional"))
    )
    (net (code "206") (name "unconnected-(U6-P$56-Pad56)") (class "Default")
      (node (ref "U6") (pin "56") (pinfunction "P$56_56") (pintype "bidirectional"))
    )
    (net (code "207") (name "unconnected-(U6-P$57-Pad57)") (class "Default")
      (node (ref "U6") (pin "57") (pinfunction "P$57_57") (pintype "bidirectional"))
    )
    (net (code "208") (name "unconnected-(U6-P$59-Pad59)") (class "Default")
      (node (ref "U6") (pin "59") (pinfunction "P$59_59") (pintype "bidirectional"))
    )
    (net (code "209") (name "unconnected-(U6-P$60-Pad60)") (class "Default")
      (node (ref "U6") (pin "60") (pinfunction "P$60_60") (pintype "bidirectional"))
    )
    (net (code "210") (name "unconnected-(U6-P$61-Pad61)") (class "Default")
      (node (ref "U6") (pin "61") (pinfunction "P$61_61") (pintype "bidirectional"))
    )
    (net (code "211") (name "unconnected-(U6-P$62-Pad62)") (class "Default")
      (node (ref "U6") (pin "62") (pinfunction "P$62_62") (pintype "bidirectional"))
    )
    (net (code "212") (name "unconnected-(U6-P$63-Pad63)") (class "Default")
      (node (ref "U6") (pin "63") (pinfunction "P$63_63") (pintype "bidirectional"))
    )
    (net (code "213") (name "unconnected-(U6-P$65-Pad65)") (class "Default")
      (node (ref "U6") (pin "65") (pinfunction "P$65_65") (pintype "bidirectional"))
    )
    (net (code "214") (name "unconnected-(U6-P$66-Pad66)") (class "Default")
      (node (ref "U6") (pin "66") (pinfunction "P$66_66") (pintype "bidirectional"))
    )
    (net (code "215") (name "unconnected-(U6-P$67-Pad67)") (class "Default")
      (node (ref "U6") (pin "67") (pinfunction "P$67_67") (pintype "bidirectional"))
    )
    (net (code "216") (name "unconnected-(U6-P$68-Pad68)") (class "Default")
      (node (ref "U6") (pin "68") (pinfunction "P$68_68") (pintype "bidirectional"))
    )
    (net (code "217") (name "unconnected-(U6-P$69-Pad69)") (class "Default")
      (node (ref "U6") (pin "69") (pinfunction "P$69_69") (pintype "bidirectional"))
    )
    (net (code "218") (name "unconnected-(X1-P$1-Pad1)") (class "Default")
      (node (ref "X1") (pin "1") (pinfunction "P$1_1") (pintype "bidirectional"))
    )
    (net (code "219") (name "unconnected-(X1-P$4-Pad4)") (class "Default")
      (node (ref "X1") (pin "4") (pinfunction "P$4_4") (pintype "bidirectional"))
    )
    (net (code "220") (name "unconnected-(X1-P$6-Pad6)") (class "Default")
      (node (ref "X1") (pin "6") (pinfunction "P$6_6") (pintype "bidirectional"))
    )
    (net (code "221") (name "unconnected-(X1-P$7-Pad7)") (class "Default")
      (node (ref "X1") (pin "7") (pinfunction "P$7_7") (pintype "bidirectional"))
    )
    (net (code "222") (name "unconnected-(X1-P$9-Pad9)") (class "Default")
      (node (ref "X1") (pin "9") (pinfunction "P$9_9") (pintype "bidirectional"))
    )
    (net (code "223") (name "unconnected-(X1-P$10-Pad10)") (class "Default")
      (node (ref "X1") (pin "10") (pinfunction "P$10_10") (pintype "bidirectional"))
    )
    (net (code "224") (name "unconnected-(X1-P$12-Pad12)") (class "Default")
      (node (ref "X1") (pin "12") (pinfunction "P$12_12") (pintype "bidirectional"))
    )
    (net (code "225") (name "unconnected-(X1-P$14-Pad14)") (class "Default")
      (node (ref "X1") (pin "14") (pinfunction "P$14_14") (pintype "bidirectional"))
    )
    (net (code "226") (name "unconnected-(X1-P$17-Pad17)") (class "Default")
      (node (ref "X1") (pin "17") (pinfunction "P$17_17") (pintype "bidirectional"))
    )
    (net (code "227") (name "unconnected-(X1-P$20-Pad20)") (class "Default")
      (node (ref "X1") (pin "20") (pinfunction "P$20_20") (pintype "bidirectional"))
    )
    (net (code "228") (name "unconnected-(X1-P$25-Pad25)") (class "Default")
      (node (ref "X1") (pin "25") (pinfunction "P$25_25") (pintype "bidirectional"))
    )
    (net (code "229") (name "unconnected-(X1-P$27-Pad27)") (class "Default")
      (node (ref "X1") (pin "27") (pinfunction "P$27_27") (pintype "bidirectional"))
    )
    (net (code "230") (name "unconnected-(X1-P$28-Pad28)") (class "Default")
      (node (ref "X1") (pin "28") (pinfunction "P$28_28") (pintype "bidirectional"))
    )
    (net (code "231") (name "unconnected-(X1-P$29-Pad29)") (class "Default")
      (node (ref "X1") (pin "29") (pinfunction "P$29_29") (pintype "bidirectional"))
    )
    (net (code "232") (name "unconnected-(X1-P$30-Pad30)") (class "Default")
      (node (ref "X1") (pin "30") (pinfunction "P$30_30") (pintype "bidirectional"))
    )
    (net (code "233") (name "unconnected-(X1-P$31-Pad31)") (class "Default")
      (node (ref "X1") (pin "31") (pinfunction "P$31_31") (pintype "bidirectional"))
    )
    (net (code "234") (name "unconnected-(X1-P$32-Pad32)") (class "Default")
      (node (ref "X1") (pin "32") (pinfunction "P$32_32") (pintype "bidirectional"))
    )
    (net (code "235") (name "unconnected-(X1-P$33-Pad33)") (class "Default")
      (node (ref "X1") (pin "33") (pinfunction "P$33_33") (pintype "bidirectional"))
    )
    (net (code "236") (name "unconnected-(X1-P$34-Pad34)") (class "Default")
      (node (ref "X1") (pin "34") (pinfunction "P$34_34") (pintype "bidirectional"))
    )
    (net (code "237") (name "unconnected-(X1-P$35-Pad35)") (class "Default")
      (node (ref "X1") (pin "35") (pinfunction "P$35_35") (pintype "bidirectional"))
    )
    (net (code "238") (name "unconnected-(X1-P$36-Pad36)") (class "Default")
      (node (ref "X1") (pin "36") (pinfunction "P$36_36") (pintype "bidirectional"))
    )
    (net (code "239") (name "unconnected-(X1-P$37-Pad37)") (class "Default")
      (node (ref "X1") (pin "37") (pinfunction "P$37_37") (pintype "bidirectional"))
    )
    (net (code "240") (name "unconnected-(X1-P$38-Pad38)") (class "Default")
      (node (ref "X1") (pin "38") (pinfunction "P$38_38") (pintype "bidirectional"))
    )
    (net (code "241") (name "unconnected-(X1-P$40-Pad40)") (class "Default")
      (node (ref "X1") (pin "40") (pinfunction "P$40_40") (pintype "bidirectional"))
    )
    (net (code "242") (name "unconnected-(X2-Pad1)") (class "Default")
      (node (ref "X2") (pin "1") (pinfunction "1_1") (pintype "passive"))
    )
    (net (code "243") (name "unconnected-(X2AA-1-Pad33)") (class "Default")
      (node (ref "X2") (pin "33") (pinfunction "1_33") (pintype "passive"))
    )
    (net (code "244") (name "unconnected-(X2AB-1-Pad34)") (class "Default")
      (node (ref "X2") (pin "34") (pinfunction "1_34") (pintype "passive"))
    )
    (net (code "245") (name "unconnected-(X2AC-1-Pad35)") (class "Default")
      (node (ref "X2") (pin "35") (pinfunction "1_35") (pintype "passive"))
    )
    (net (code "246") (name "unconnected-(X2AD-1-Pad36)") (class "Default")
      (node (ref "X2") (pin "36") (pinfunction "1_36") (pintype "passive"))
    )
    (net (code "247") (name "unconnected-(X2AE-1-Pad37)") (class "Default")
      (node (ref "X2") (pin "37") (pinfunction "1_37") (pintype "passive"))
    )
    (net (code "248") (name "unconnected-(X2AF-1-Pad38)") (class "Default")
      (node (ref "X2") (pin "38") (pinfunction "1_38") (pintype "passive"))
    )
    (net (code "249") (name "unconnected-(X2AG-1-Pad39)") (class "Default")
      (node (ref "X2") (pin "39") (pinfunction "1_39") (pintype "passive"))
    )
    (net (code "250") (name "unconnected-(X2AH-1-Pad4)") (class "Default")
      (node (ref "X2") (pin "4") (pinfunction "1_4") (pintype "passive"))
    )
    (net (code "251") (name "unconnected-(X2AI-1-Pad40)") (class "Default")
      (node (ref "X2") (pin "40") (pinfunction "1_40") (pintype "passive"))
    )
    (net (code "252") (name "unconnected-(X2AJ-1-Pad5)") (class "Default")
      (node (ref "X2") (pin "5") (pinfunction "1_5") (pintype "passive"))
    )
    (net (code "253") (name "unconnected-(X2AK-1-Pad6)") (class "Default")
      (node (ref "X2") (pin "6") (pinfunction "1_6") (pintype "passive"))
    )
    (net (code "254") (name "unconnected-(X2AL-1-Pad7)") (class "Default")
      (node (ref "X2") (pin "7") (pinfunction "1_7") (pintype "passive"))
    )
    (net (code "255") (name "unconnected-(X2AM-1-Pad8)") (class "Default")
      (node (ref "X2") (pin "8") (pinfunction "1_8") (pintype "passive"))
    )
    (net (code "256") (name "unconnected-(X2AN-1-Pad9)") (class "Default")
      (node (ref "X2") (pin "9") (pinfunction "1_9") (pintype "passive"))
    )
    (net (code "257") (name "unconnected-(X2B-1-Pad10)") (class "Default")
      (node (ref "X2") (pin "10") (pinfunction "1_10") (pintype "passive"))
    )
    (net (code "258") (name "unconnected-(X2C-1-Pad11)") (class "Default")
      (node (ref "X2") (pin "11") (pinfunction "1_11") (pintype "passive"))
    )
    (net (code "259") (name "unconnected-(X2D-1-Pad12)") (class "Default")
      (node (ref "X2") (pin "12") (pinfunction "1_12") (pintype "passive"))
    )
    (net (code "260") (name "unconnected-(X2E-1-Pad13)") (class "Default")
      (node (ref "X2") (pin "13") (pinfunction "1_13") (pintype "passive"))
    )
    (net (code "261") (name "unconnected-(X2F-1-Pad14)") (class "Default")
      (node (ref "X2") (pin "14") (pinfunction "1_14") (pintype "passive"))
    )
    (net (code "262") (name "unconnected-(X2G-1-Pad15)") (class "Default")
      (node (ref "X2") (pin "15") (pinfunction "1_15") (pintype "passive"))
    )
    (net (code "263") (name "unconnected-(X2H-1-Pad16)") (class "Default")
      (node (ref "X2") (pin "16") (pinfunction "1_16") (pintype "passive"))
    )
    (net (code "264") (name "unconnected-(X2I-1-Pad17)") (class "Default")
      (node (ref "X2") (pin "17") (pinfunction "1_17") (pintype "passive"))
    )
    (net (code "265") (name "unconnected-(X2J-1-Pad18)") (class "Default")
      (node (ref "X2") (pin "18") (pinfunction "1_18") (pintype "passive"))
    )
    (net (code "266") (name "unconnected-(X2K-1-Pad19)") (class "Default")
      (node (ref "X2") (pin "19") (pinfunction "1_19") (pintype "passive"))
    )
    (net (code "267") (name "unconnected-(X2L-1-Pad2)") (class "Default")
      (node (ref "X2") (pin "2") (pinfunction "1_2") (pintype "passive"))
    )
    (net (code "268") (name "unconnected-(X2M-1-Pad20)") (class "Default")
      (node (ref "X2") (pin "20") (pinfunction "1_20") (pintype "passive"))
    )
    (net (code "269") (name "unconnected-(X2N-1-Pad21)") (class "Default")
      (node (ref "X2") (pin "21") (pinfunction "1_21") (pintype "passive"))
    )
    (net (code "270") (name "unconnected-(X2O-1-Pad22)") (class "Default")
      (node (ref "X2") (pin "22") (pinfunction "1_22") (pintype "passive"))
    )
    (net (code "271") (name "unconnected-(X2P-1-Pad23)") (class "Default")
      (node (ref "X2") (pin "23") (pinfunction "1_23") (pintype "passive"))
    )
    (net (code "272") (name "unconnected-(X2Q-1-Pad24)") (class "Default")
      (node (ref "X2") (pin "24") (pinfunction "1_24") (pintype "passive"))
    )
    (net (code "273") (name "unconnected-(X2R-1-Pad25)") (class "Default")
      (node (ref "X2") (pin "25") (pinfunction "1_25") (pintype "passive"))
    )
    (net (code "274") (name "unconnected-(X2S-1-Pad26)") (class "Default")
      (node (ref "X2") (pin "26") (pinfunction "1_26") (pintype "passive"))
    )
    (net (code "275") (name "unconnected-(X2T-1-Pad27)") (class "Default")
      (node (ref "X2") (pin "27") (pinfunction "1_27") (pintype "passive"))
    )
    (net (code "276") (name "unconnected-(X2U-1-Pad28)") (class "Default")
      (node (ref "X2") (pin "28") (pinfunction "1_28") (pintype "passive"))
    )
    (net (code "277") (name "unconnected-(X2V-1-Pad29)") (class "Default")
      (node (ref "X2") (pin "29") (pinfunction "1_29") (pintype "passive"))
    )
    (net (code "278") (name "unconnected-(X2W-1-Pad3)") (class "Default")
      (node (ref "X2") (pin "3") (pinfunction "1_3") (pintype "passive"))
    )
    (net (code "279") (name "unconnected-(X2X-1-Pad30)") (class "Default")
      (node (ref "X2") (pin "30") (pinfunction "1_30") (pintype "passive"))
    )
    (net (code "280") (name "unconnected-(X2Y-1-Pad31)") (class "Default")
      (node (ref "X2") (pin "31") (pinfunction "1_31") (pintype "passive"))
    )
    (net (code "281") (name "unconnected-(X2Z-1-Pad32)") (class "Default")
      (node (ref "X2") (pin "32") (pinfunction "1_32") (pintype "passive"))
    )
  )
)
